# board.net
KiCad netlist of a schematic drawn in EAGLE
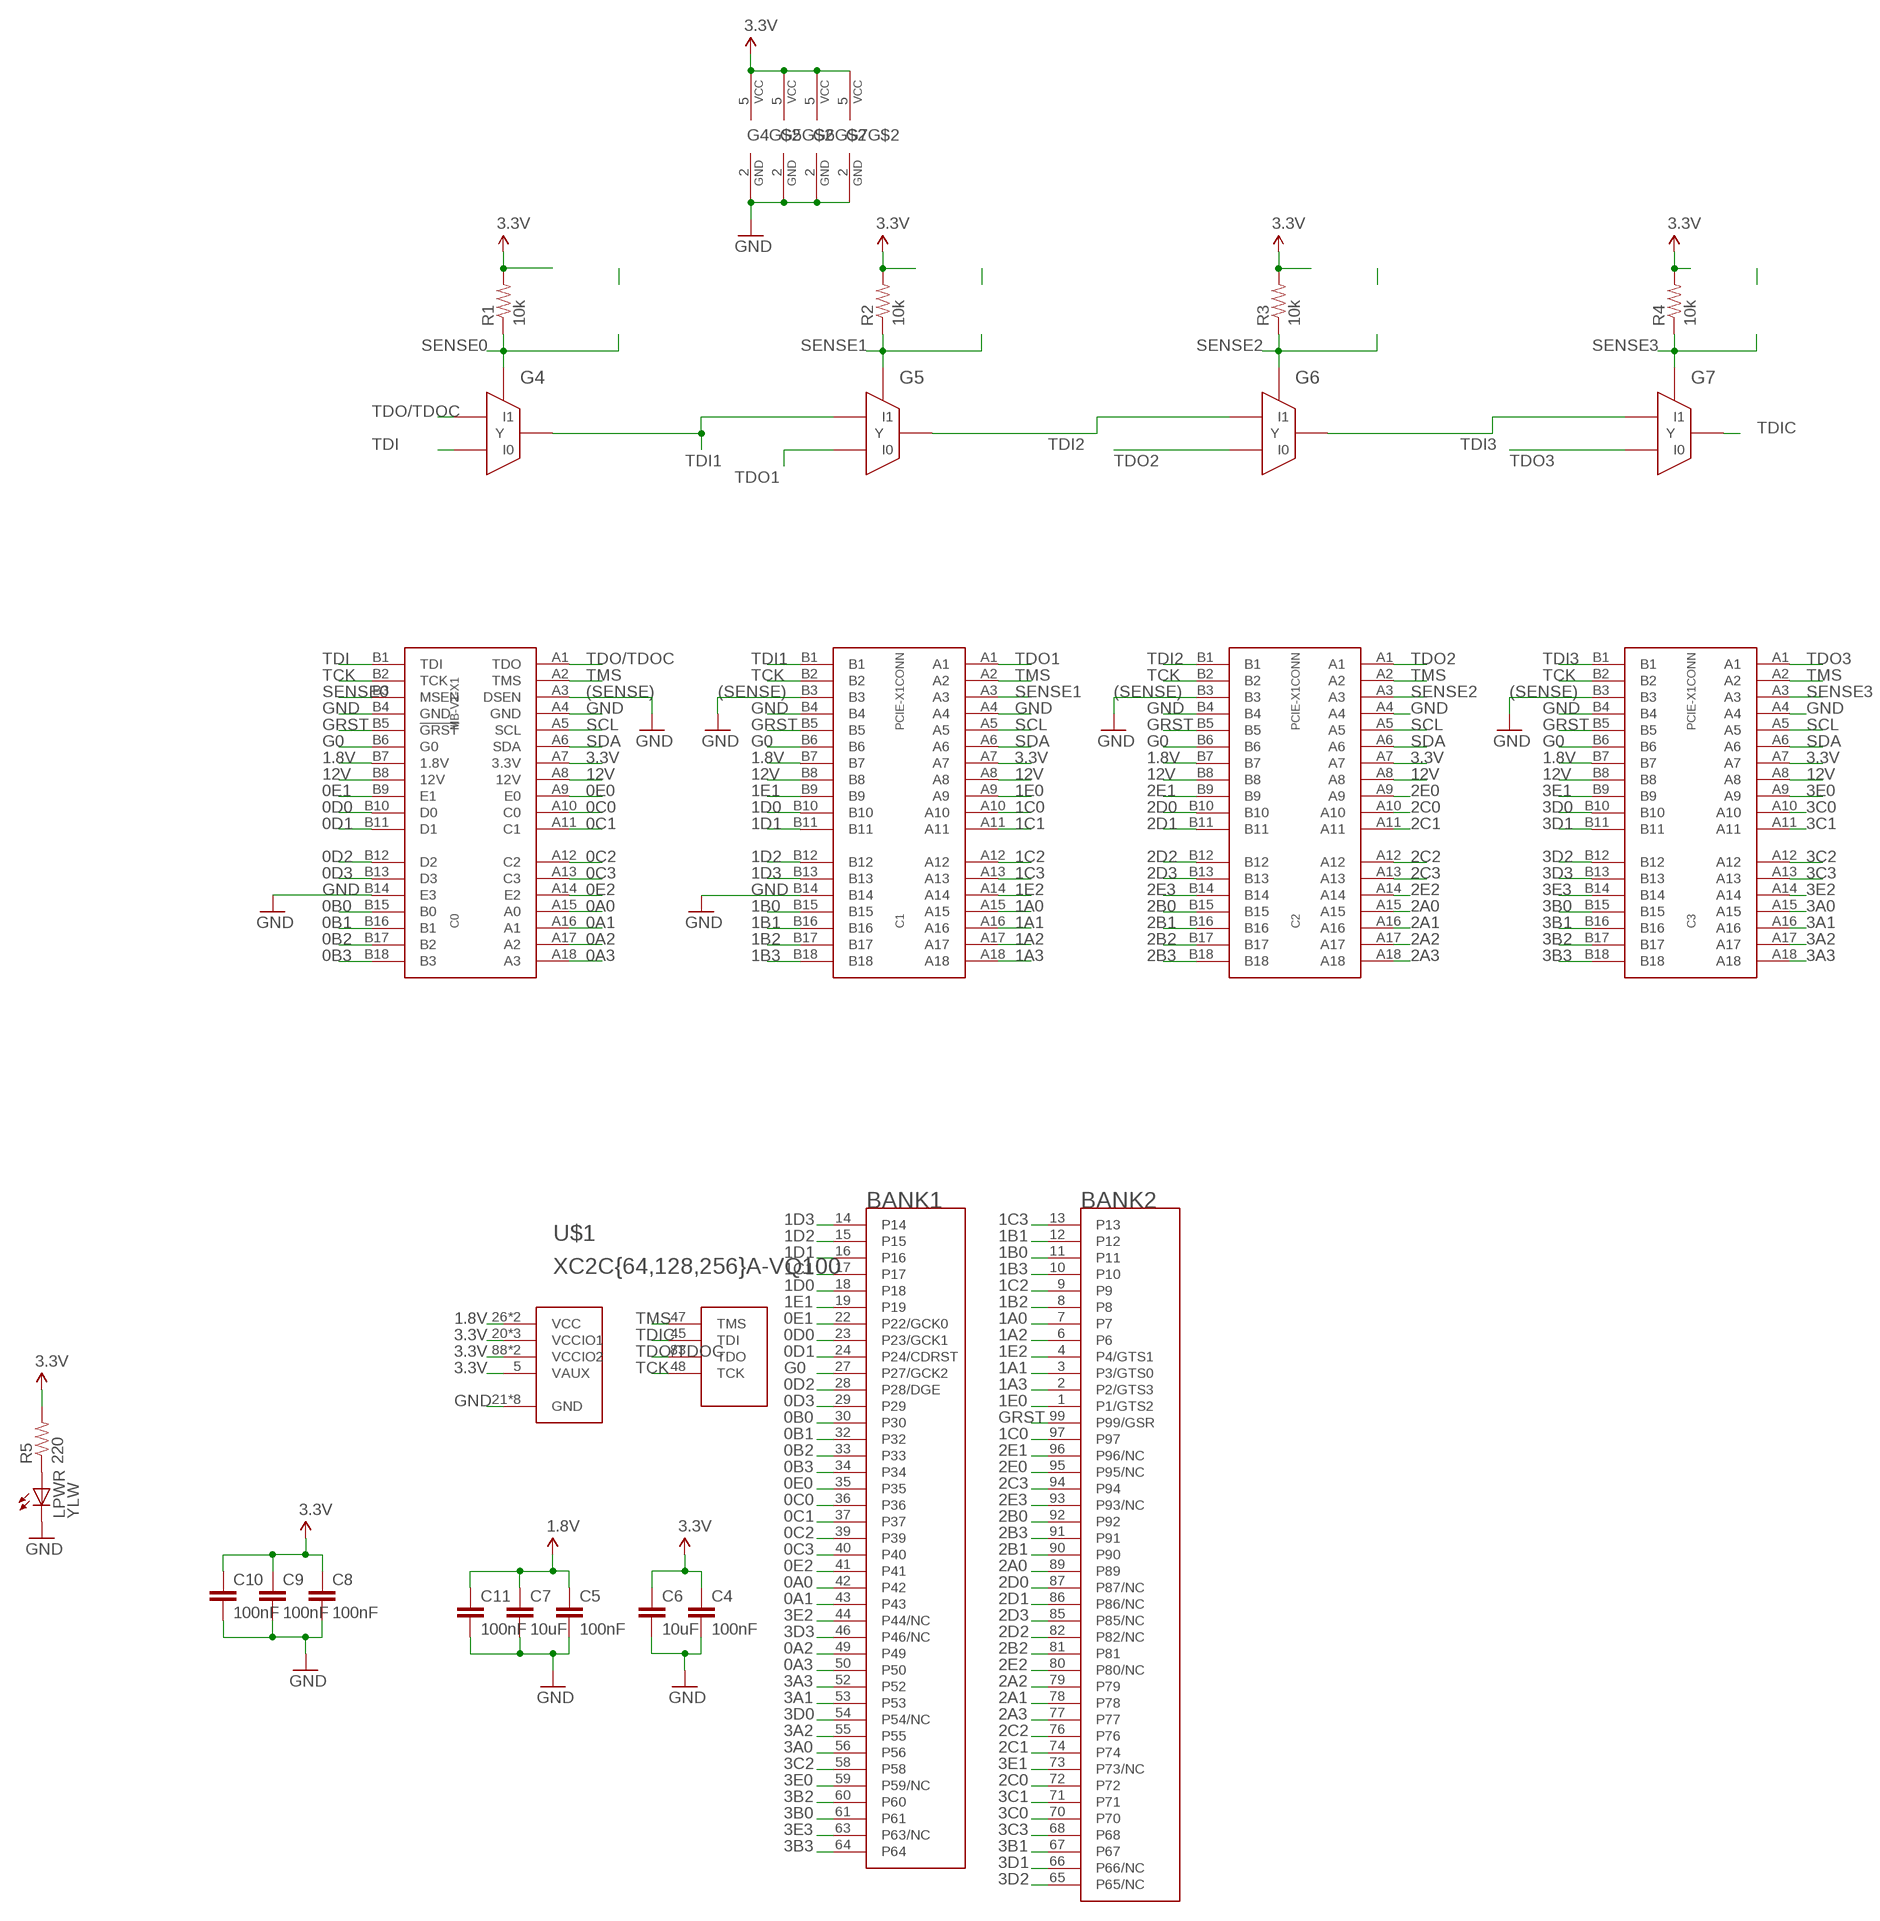
[diagram p0: schematic, sheet 1]

(export (version "E")
  (design (tool "Eeschema 10.0.6"))
  (components
    (comp (ref "C0")
      (value "MB-V1-X1")
      (footprint "eagle-import:PCIE-X1-EDGE")
      (libsource (lib "eagle-import") (part "MB-V1-X1"))
    )
    (comp (ref "C1")
      (value "PCIE-X1CONN")
      (footprint "eagle-import:PCIE-X1-CONN")
      (libsource (lib "eagle-import") (part "PCIE-X1CONN"))
    )
    (comp (ref "C2")
      (value "PCIE-X1CONN")
      (footprint "eagle-import:PCIE-X1-CONN")
      (libsource (lib "eagle-import") (part "PCIE-X1CONN"))
    )
    (comp (ref "C3")
      (value "PCIE-X1CONN")
      (footprint "eagle-import:PCIE-X1-CONN")
      (libsource (lib "eagle-import") (part "PCIE-X1CONN"))
    )
    (comp (ref "C4")
      (value "100nF")
      (footprint "eagle-import:0402-CAP")
      (libsource (lib "eagle-import") (part "CAP0402-CAP"))
    )
    (comp (ref "C5")
      (value "100nF")
      (footprint "eagle-import:0402-CAP")
      (libsource (lib "eagle-import") (part "CAP0402-CAP"))
    )
    (comp (ref "C6")
      (value "10uF")
      (footprint "eagle-import:0805")
      (libsource (lib "eagle-import") (part "CAP0805"))
    )
    (comp (ref "C7")
      (value "10uF")
      (footprint "eagle-import:0805")
      (libsource (lib "eagle-import") (part "CAP0805"))
    )
    (comp (ref "C8")
      (value "100nF")
      (footprint "eagle-import:0402-CAP")
      (libsource (lib "eagle-import") (part "CAP0402-CAP"))
    )
    (comp (ref "C9")
      (value "100nF")
      (footprint "eagle-import:0402-CAP")
      (libsource (lib "eagle-import") (part "CAP0402-CAP"))
    )
    (comp (ref "C10")
      (value "100nF")
      (footprint "eagle-import:0402-CAP")
      (libsource (lib "eagle-import") (part "CAP0402-CAP"))
    )
    (comp (ref "C11")
      (value "100nF")
      (footprint "eagle-import:0402-CAP")
      (libsource (lib "eagle-import") (part "CAP0402-CAP"))
    )
    (comp (ref "G4")
      (value "74G157")
      (footprint "eagle-import:SOT363")
      (libsource (lib "eagle-import") (part "74G157"))
    )
    (comp (ref "G5")
      (value "74G157")
      (footprint "eagle-import:SOT363")
      (libsource (lib "eagle-import") (part "74G157"))
    )
    (comp (ref "G6")
      (value "74G157")
      (footprint "eagle-import:SOT363")
      (libsource (lib "eagle-import") (part "74G157"))
    )
    (comp (ref "G7")
      (value "74G157")
      (footprint "eagle-import:SOT363")
      (libsource (lib "eagle-import") (part "74G157"))
    )
    (comp (ref "LPWR")
      (value "YLW")
      (footprint "eagle-import:LED-0603")
      (libsource (lib "eagle-import") (part "LED-RED0603"))
    )
    (comp (ref "R1")
      (value "10k")
      (footprint "eagle-import:0603-RES")
      (libsource (lib "eagle-import") (part "kmod-passives_RESISTOR0603"))
    )
    (comp (ref "R2")
      (value "10k")
      (footprint "eagle-import:0603-RES")
      (libsource (lib "eagle-import") (part "kmod-passives_RESISTOR0603"))
    )
    (comp (ref "R3")
      (value "10k")
      (footprint "eagle-import:0603-RES")
      (libsource (lib "eagle-import") (part "kmod-passives_RESISTOR0603"))
    )
    (comp (ref "R4")
      (value "10k")
      (footprint "eagle-import:0603-RES")
      (libsource (lib "eagle-import") (part "kmod-passives_RESISTOR0603"))
    )
    (comp (ref "R5")
      (value "220")
      (footprint "eagle-import:0603-RES")
      (libsource (lib "eagle-import") (part "RESISTOR0603"))
    )
    (comp (ref "U$1")
      (value "XC2C{64,128,256}A-VQ100")
      (footprint "eagle-import:XILINX_TQ100")
      (libsource (lib "eagle-import") (part "XC2C{64,128,256}A-VQ100"))
    )
  )
  (nets
    (net (code "1") (name "/0A0") (class "Default")
      (node (ref "C0") (pin "A15") (pinfunction "A0_A15") (pintype "bidirectional"))
      (node (ref "U$1") (pin "42") (pinfunction "P42_42") (pintype "bidirectional"))
    )
    (net (code "2") (name "/0A1") (class "Default")
      (node (ref "C0") (pin "A16") (pinfunction "A1_A16") (pintype "bidirectional"))
      (node (ref "U$1") (pin "43") (pinfunction "P43_43") (pintype "bidirectional"))
    )
    (net (code "3") (name "/0A2") (class "Default")
      (node (ref "C0") (pin "A17") (pinfunction "A2_A17") (pintype "bidirectional"))
      (node (ref "U$1") (pin "49") (pinfunction "P49_49") (pintype "bidirectional"))
    )
    (net (code "4") (name "/0A3") (class "Default")
      (node (ref "C0") (pin "A18") (pinfunction "A3_A18") (pintype "bidirectional"))
      (node (ref "U$1") (pin "50") (pinfunction "P50_50") (pintype "bidirectional"))
    )
    (net (code "5") (name "/0B0") (class "Default")
      (node (ref "C0") (pin "B15") (pinfunction "B0_B15") (pintype "bidirectional"))
      (node (ref "U$1") (pin "30") (pinfunction "P30_30") (pintype "bidirectional"))
    )
    (net (code "6") (name "/0B1") (class "Default")
      (node (ref "C0") (pin "B16") (pinfunction "B1_B16") (pintype "bidirectional"))
      (node (ref "U$1") (pin "32") (pinfunction "P32_32") (pintype "bidirectional"))
    )
    (net (code "7") (name "/0B2") (class "Default")
      (node (ref "C0") (pin "B17") (pinfunction "B2_B17") (pintype "bidirectional"))
      (node (ref "U$1") (pin "33") (pinfunction "P33_33") (pintype "bidirectional"))
    )
    (net (code "8") (name "/0B3") (class "Default")
      (node (ref "C0") (pin "B18") (pinfunction "B3_B18") (pintype "bidirectional"))
      (node (ref "U$1") (pin "34") (pinfunction "P34_34") (pintype "bidirectional"))
    )
    (net (code "9") (name "/0C0") (class "Default")
      (node (ref "C0") (pin "A10") (pinfunction "C0_A10") (pintype "bidirectional"))
      (node (ref "U$1") (pin "36") (pinfunction "P36_36") (pintype "bidirectional"))
    )
    (net (code "10") (name "/0C1") (class "Default")
      (node (ref "C0") (pin "A11") (pinfunction "C1_A11") (pintype "bidirectional"))
      (node (ref "U$1") (pin "37") (pinfunction "P37_37") (pintype "bidirectional"))
    )
    (net (code "11") (name "/0C2") (class "Default")
      (node (ref "C0") (pin "A12") (pinfunction "C2_A12") (pintype "bidirectional"))
      (node (ref "U$1") (pin "39") (pinfunction "P39_39") (pintype "bidirectional"))
    )
    (net (code "12") (name "/0C3") (class "Default")
      (node (ref "C0") (pin "A13") (pinfunction "C3_A13") (pintype "bidirectional"))
      (node (ref "U$1") (pin "40") (pinfunction "P40_40") (pintype "bidirectional"))
    )
    (net (code "13") (name "/0D0") (class "Default")
      (node (ref "C0") (pin "B10") (pinfunction "D0_B10") (pintype "bidirectional"))
      (node (ref "U$1") (pin "23") (pinfunction "P23/GCK1_23") (pintype "bidirectional"))
    )
    (net (code "14") (name "/0D1") (class "Default")
      (node (ref "C0") (pin "B11") (pinfunction "D1_B11") (pintype "bidirectional"))
      (node (ref "U$1") (pin "24") (pinfunction "P24/CDRST_24") (pintype "bidirectional"))
    )
    (net (code "15") (name "/0D2") (class "Default")
      (node (ref "C0") (pin "B12") (pinfunction "D2_B12") (pintype "bidirectional"))
      (node (ref "U$1") (pin "28") (pinfunction "P28/DGE_28") (pintype "bidirectional"))
    )
    (net (code "16") (name "/0D3") (class "Default")
      (node (ref "C0") (pin "B13") (pinfunction "D3_B13") (pintype "bidirectional"))
      (node (ref "U$1") (pin "29") (pinfunction "P29_29") (pintype "bidirectional"))
    )
    (net (code "17") (name "/0E0") (class "Default")
      (node (ref "C0") (pin "A9") (pinfunction "E0_A9") (pintype "bidirectional"))
      (node (ref "U$1") (pin "35") (pinfunction "P35_35") (pintype "bidirectional"))
    )
    (net (code "18") (name "/0E1") (class "Default")
      (node (ref "C0") (pin "B9") (pinfunction "E1_B9") (pintype "bidirectional"))
      (node (ref "U$1") (pin "22") (pinfunction "P22/GCK0_22") (pintype "bidirectional"))
    )
    (net (code "19") (name "/0E2") (class "Default")
      (node (ref "C0") (pin "A14") (pinfunction "E2_A14") (pintype "bidirectional"))
      (node (ref "U$1") (pin "41") (pinfunction "P41_41") (pintype "bidirectional"))
    )
    (net (code "20") (name "/1A0") (class "Default")
      (node (ref "C1") (pin "A15") (pinfunction "A15_A15") (pintype "bidirectional"))
      (node (ref "U$1") (pin "7") (pinfunction "P7_7") (pintype "bidirectional"))
    )
    (net (code "21") (name "/1A1") (class "Default")
      (node (ref "C1") (pin "A16") (pinfunction "A16_A16") (pintype "bidirectional"))
      (node (ref "U$1") (pin "3") (pinfunction "P3/GTS0_3") (pintype "bidirectional"))
    )
    (net (code "22") (name "/1A2") (class "Default")
      (node (ref "C1") (pin "A17") (pinfunction "A17_A17") (pintype "bidirectional"))
      (node (ref "U$1") (pin "6") (pinfunction "P6_6") (pintype "bidirectional"))
    )
    (net (code "23") (name "/1A3") (class "Default")
      (node (ref "C1") (pin "A18") (pinfunction "A18_A18") (pintype "bidirectional"))
      (node (ref "U$1") (pin "2") (pinfunction "P2/GTS3_2") (pintype "bidirectional"))
    )
    (net (code "24") (name "/1B0") (class "Default")
      (node (ref "C1") (pin "B15") (pinfunction "B15_B15") (pintype "bidirectional"))
      (node (ref "U$1") (pin "11") (pinfunction "P11_11") (pintype "bidirectional"))
    )
    (net (code "25") (name "/1B1") (class "Default")
      (node (ref "C1") (pin "B16") (pinfunction "B16_B16") (pintype "bidirectional"))
      (node (ref "U$1") (pin "12") (pinfunction "P12_12") (pintype "bidirectional"))
    )
    (net (code "26") (name "/1B2") (class "Default")
      (node (ref "C1") (pin "B17") (pinfunction "B17_B17") (pintype "bidirectional"))
      (node (ref "U$1") (pin "8") (pinfunction "P8_8") (pintype "bidirectional"))
    )
    (net (code "27") (name "/1B3") (class "Default")
      (node (ref "C1") (pin "B18") (pinfunction "B18_B18") (pintype "bidirectional"))
      (node (ref "U$1") (pin "10") (pinfunction "P10_10") (pintype "bidirectional"))
    )
    (net (code "28") (name "/1C0") (class "Default")
      (node (ref "C1") (pin "A10") (pinfunction "A10_A10") (pintype "bidirectional"))
      (node (ref "U$1") (pin "97") (pinfunction "P97_97") (pintype "bidirectional"))
    )
    (net (code "29") (name "/1C1") (class "Default")
      (node (ref "C1") (pin "A11") (pinfunction "A11_A11") (pintype "bidirectional"))
      (node (ref "U$1") (pin "17") (pinfunction "P17_17") (pintype "bidirectional"))
    )
    (net (code "30") (name "/1C2") (class "Default")
      (node (ref "C1") (pin "A12") (pinfunction "A12_A12") (pintype "bidirectional"))
      (node (ref "U$1") (pin "9") (pinfunction "P9_9") (pintype "bidirectional"))
    )
    (net (code "31") (name "/1C3") (class "Default")
      (node (ref "C1") (pin "A13") (pinfunction "A13_A13") (pintype "bidirectional"))
      (node (ref "U$1") (pin "13") (pinfunction "P13_13") (pintype "bidirectional"))
    )
    (net (code "32") (name "/1D0") (class "Default")
      (node (ref "C1") (pin "B10") (pinfunction "B10_B10") (pintype "bidirectional"))
      (node (ref "U$1") (pin "18") (pinfunction "P18_18") (pintype "bidirectional"))
    )
    (net (code "33") (name "/1D1") (class "Default")
      (node (ref "C1") (pin "B11") (pinfunction "B11_B11") (pintype "bidirectional"))
      (node (ref "U$1") (pin "16") (pinfunction "P16_16") (pintype "bidirectional"))
    )
    (net (code "34") (name "/1D2") (class "Default")
      (node (ref "C1") (pin "B12") (pinfunction "B12_B12") (pintype "bidirectional"))
      (node (ref "U$1") (pin "15") (pinfunction "P15_15") (pintype "bidirectional"))
    )
    (net (code "35") (name "/1D3") (class "Default")
      (node (ref "C1") (pin "B13") (pinfunction "B13_B13") (pintype "bidirectional"))
      (node (ref "U$1") (pin "14") (pinfunction "P14_14") (pintype "bidirectional"))
    )
    (net (code "36") (name "/1E0") (class "Default")
      (node (ref "C1") (pin "A9") (pinfunction "A9_A9") (pintype "bidirectional"))
      (node (ref "U$1") (pin "1") (pinfunction "P1/GTS2_1") (pintype "bidirectional"))
    )
    (net (code "37") (name "/1E1") (class "Default")
      (node (ref "C1") (pin "B9") (pinfunction "B9_B9") (pintype "bidirectional"))
      (node (ref "U$1") (pin "19") (pinfunction "P19_19") (pintype "bidirectional"))
    )
    (net (code "38") (name "/1E2") (class "Default")
      (node (ref "C1") (pin "A14") (pinfunction "A14_A14") (pintype "bidirectional"))
      (node (ref "U$1") (pin "4") (pinfunction "P4/GTS1_4") (pintype "bidirectional"))
    )
    (net (code "39") (name "/2A0") (class "Default")
      (node (ref "C2") (pin "A15") (pinfunction "A15_A15") (pintype "bidirectional"))
      (node (ref "U$1") (pin "89") (pinfunction "P89_89") (pintype "bidirectional"))
    )
    (net (code "40") (name "/2A1") (class "Default")
      (node (ref "C2") (pin "A16") (pinfunction "A16_A16") (pintype "bidirectional"))
      (node (ref "U$1") (pin "78") (pinfunction "P78_78") (pintype "bidirectional"))
    )
    (net (code "41") (name "/2A2") (class "Default")
      (node (ref "C2") (pin "A17") (pinfunction "A17_A17") (pintype "bidirectional"))
      (node (ref "U$1") (pin "79") (pinfunction "P79_79") (pintype "bidirectional"))
    )
    (net (code "42") (name "/2A3") (class "Default")
      (node (ref "C2") (pin "A18") (pinfunction "A18_A18") (pintype "bidirectional"))
      (node (ref "U$1") (pin "77") (pinfunction "P77_77") (pintype "bidirectional"))
    )
    (net (code "43") (name "/2B0") (class "Default")
      (node (ref "C2") (pin "B15") (pinfunction "B15_B15") (pintype "bidirectional"))
      (node (ref "U$1") (pin "92") (pinfunction "P92_92") (pintype "bidirectional"))
    )
    (net (code "44") (name "/2B1") (class "Default")
      (node (ref "C2") (pin "B16") (pinfunction "B16_B16") (pintype "bidirectional"))
      (node (ref "U$1") (pin "90") (pinfunction "P90_90") (pintype "bidirectional"))
    )
    (net (code "45") (name "/2B2") (class "Default")
      (node (ref "C2") (pin "B17") (pinfunction "B17_B17") (pintype "bidirectional"))
      (node (ref "U$1") (pin "81") (pinfunction "P81_81") (pintype "bidirectional"))
    )
    (net (code "46") (name "/2B3") (class "Default")
      (node (ref "C2") (pin "B18") (pinfunction "B18_B18") (pintype "bidirectional"))
      (node (ref "U$1") (pin "91") (pinfunction "P91_91") (pintype "bidirectional"))
    )
    (net (code "47") (name "/2C0") (class "Default")
      (node (ref "C2") (pin "A10") (pinfunction "A10_A10") (pintype "bidirectional"))
      (node (ref "U$1") (pin "72") (pinfunction "P72_72") (pintype "bidirectional"))
    )
    (net (code "48") (name "/2C1") (class "Default")
      (node (ref "C2") (pin "A11") (pinfunction "A11_A11") (pintype "bidirectional"))
      (node (ref "U$1") (pin "74") (pinfunction "P74_74") (pintype "bidirectional"))
    )
    (net (code "49") (name "/2C2") (class "Default")
      (node (ref "C2") (pin "A12") (pinfunction "A12_A12") (pintype "bidirectional"))
      (node (ref "U$1") (pin "76") (pinfunction "P76_76") (pintype "bidirectional"))
    )
    (net (code "50") (name "/2C3") (class "Default")
      (node (ref "C2") (pin "A13") (pinfunction "A13_A13") (pintype "bidirectional"))
      (node (ref "U$1") (pin "94") (pinfunction "P94_94") (pintype "bidirectional"))
    )
    (net (code "51") (name "/2D0") (class "Default")
      (node (ref "C2") (pin "B10") (pinfunction "B10_B10") (pintype "bidirectional"))
      (node (ref "U$1") (pin "87") (pinfunction "P87/NC_87") (pintype "bidirectional"))
    )
    (net (code "52") (name "/2D1") (class "Default")
      (node (ref "C2") (pin "B11") (pinfunction "B11_B11") (pintype "bidirectional"))
      (node (ref "U$1") (pin "86") (pinfunction "P86/NC_86") (pintype "bidirectional"))
    )
    (net (code "53") (name "/2D2") (class "Default")
      (node (ref "C2") (pin "B12") (pinfunction "B12_B12") (pintype "bidirectional"))
      (node (ref "U$1") (pin "82") (pinfunction "P82/NC_82") (pintype "bidirectional"))
    )
    (net (code "54") (name "/2D3") (class "Default")
      (node (ref "C2") (pin "B13") (pinfunction "B13_B13") (pintype "bidirectional"))
      (node (ref "U$1") (pin "85") (pinfunction "P85/NC_85") (pintype "bidirectional"))
    )
    (net (code "55") (name "/2E0") (class "Default")
      (node (ref "C2") (pin "A9") (pinfunction "A9_A9") (pintype "bidirectional"))
      (node (ref "U$1") (pin "95") (pinfunction "P95/NC_95") (pintype "bidirectional"))
    )
    (net (code "56") (name "/2E1") (class "Default")
      (node (ref "C2") (pin "B9") (pinfunction "B9_B9") (pintype "bidirectional"))
      (node (ref "U$1") (pin "96") (pinfunction "P96/NC_96") (pintype "bidirectional"))
    )
    (net (code "57") (name "/2E2") (class "Default")
      (node (ref "C2") (pin "A14") (pinfunction "A14_A14") (pintype "bidirectional"))
      (node (ref "U$1") (pin "80") (pinfunction "P80/NC_80") (pintype "bidirectional"))
    )
    (net (code "58") (name "/2E3") (class "Default")
      (node (ref "C2") (pin "B14") (pinfunction "B14_B14") (pintype "bidirectional"))
      (node (ref "U$1") (pin "93") (pinfunction "P93/NC_93") (pintype "bidirectional"))
    )
    (net (code "59") (name "/3A0") (class "Default")
      (node (ref "C3") (pin "A15") (pinfunction "A15_A15") (pintype "bidirectional"))
      (node (ref "U$1") (pin "56") (pinfunction "P56_56") (pintype "bidirectional"))
    )
    (net (code "60") (name "/3A1") (class "Default")
      (node (ref "C3") (pin "A16") (pinfunction "A16_A16") (pintype "bidirectional"))
      (node (ref "U$1") (pin "53") (pinfunction "P53_53") (pintype "bidirectional"))
    )
    (net (code "61") (name "/3A2") (class "Default")
      (node (ref "C3") (pin "A17") (pinfunction "A17_A17") (pintype "bidirectional"))
      (node (ref "U$1") (pin "55") (pinfunction "P55_55") (pintype "bidirectional"))
    )
    (net (code "62") (name "/3A3") (class "Default")
      (node (ref "C3") (pin "A18") (pinfunction "A18_A18") (pintype "bidirectional"))
      (node (ref "U$1") (pin "52") (pinfunction "P52_52") (pintype "bidirectional"))
    )
    (net (code "63") (name "/3B0") (class "Default")
      (node (ref "C3") (pin "B15") (pinfunction "B15_B15") (pintype "bidirectional"))
      (node (ref "U$1") (pin "61") (pinfunction "P61_61") (pintype "bidirectional"))
    )
    (net (code "64") (name "/3B1") (class "Default")
      (node (ref "C3") (pin "B16") (pinfunction "B16_B16") (pintype "bidirectional"))
      (node (ref "U$1") (pin "67") (pinfunction "P67_67") (pintype "bidirectional"))
    )
    (net (code "65") (name "/3B2") (class "Default")
      (node (ref "C3") (pin "B17") (pinfunction "B17_B17") (pintype "bidirectional"))
      (node (ref "U$1") (pin "60") (pinfunction "P60_60") (pintype "bidirectional"))
    )
    (net (code "66") (name "/3B3") (class "Default")
      (node (ref "C3") (pin "B18") (pinfunction "B18_B18") (pintype "bidirectional"))
      (node (ref "U$1") (pin "64") (pinfunction "P64_64") (pintype "bidirectional"))
    )
    (net (code "67") (name "/3C0") (class "Default")
      (node (ref "C3") (pin "A10") (pinfunction "A10_A10") (pintype "bidirectional"))
      (node (ref "U$1") (pin "70") (pinfunction "P70_70") (pintype "bidirectional"))
    )
    (net (code "68") (name "/3C1") (class "Default")
      (node (ref "C3") (pin "A11") (pinfunction "A11_A11") (pintype "bidirectional"))
      (node (ref "U$1") (pin "71") (pinfunction "P71_71") (pintype "bidirectional"))
    )
    (net (code "69") (name "/3C2") (class "Default")
      (node (ref "C3") (pin "A12") (pinfunction "A12_A12") (pintype "bidirectional"))
      (node (ref "U$1") (pin "58") (pinfunction "P58_58") (pintype "bidirectional"))
    )
    (net (code "70") (name "/3C3") (class "Default")
      (node (ref "C3") (pin "A13") (pinfunction "A13_A13") (pintype "bidirectional"))
      (node (ref "U$1") (pin "68") (pinfunction "P68_68") (pintype "bidirectional"))
    )
    (net (code "71") (name "/3D0") (class "Default")
      (node (ref "C3") (pin "B10") (pinfunction "B10_B10") (pintype "bidirectional"))
      (node (ref "U$1") (pin "54") (pinfunction "P54/NC_54") (pintype "bidirectional"))
    )
    (net (code "72") (name "/3D1") (class "Default")
      (node (ref "C3") (pin "B11") (pinfunction "B11_B11") (pintype "bidirectional"))
      (node (ref "U$1") (pin "66") (pinfunction "P66/NC_66") (pintype "bidirectional"))
    )
    (net (code "73") (name "/3D2") (class "Default")
      (node (ref "C3") (pin "B12") (pinfunction "B12_B12") (pintype "bidirectional"))
      (node (ref "U$1") (pin "65") (pinfunction "P65/NC_65") (pintype "bidirectional"))
    )
    (net (code "74") (name "/3D3") (class "Default")
      (node (ref "C3") (pin "B13") (pinfunction "B13_B13") (pintype "bidirectional"))
      (node (ref "U$1") (pin "46") (pinfunction "P46/NC_46") (pintype "bidirectional"))
    )
    (net (code "75") (name "/3E0") (class "Default")
      (node (ref "C3") (pin "A9") (pinfunction "A9_A9") (pintype "bidirectional"))
      (node (ref "U$1") (pin "59") (pinfunction "P59/NC_59") (pintype "bidirectional"))
    )
    (net (code "76") (name "/3E1") (class "Default")
      (node (ref "C3") (pin "B9") (pinfunction "B9_B9") (pintype "bidirectional"))
      (node (ref "U$1") (pin "73") (pinfunction "P73/NC_73") (pintype "bidirectional"))
    )
    (net (code "77") (name "/3E2") (class "Default")
      (node (ref "C3") (pin "A14") (pinfunction "A14_A14") (pintype "bidirectional"))
      (node (ref "U$1") (pin "44") (pinfunction "P44/NC_44") (pintype "bidirectional"))
    )
    (net (code "78") (name "/3E3") (class "Default")
      (node (ref "C3") (pin "B14") (pinfunction "B14_B14") (pintype "bidirectional"))
      (node (ref "U$1") (pin "63") (pinfunction "P63/NC_63") (pintype "bidirectional"))
    )
    (net (code "79") (name "/12V") (class "Default")
      (node (ref "C0") (pin "A8") (pinfunction "12V_A8") (pintype "bidirectional"))
      (node (ref "C0") (pin "B8") (pinfunction "12V_B8") (pintype "bidirectional"))
      (node (ref "C1") (pin "A8") (pinfunction "A8_A8") (pintype "bidirectional"))
      (node (ref "C1") (pin "B8") (pinfunction "B8_B8") (pintype "bidirectional"))
      (node (ref "C2") (pin "A8") (pinfunction "A8_A8") (pintype "bidirectional"))
      (node (ref "C2") (pin "B8") (pinfunction "B8_B8") (pintype "bidirectional"))
      (node (ref "C3") (pin "A8") (pinfunction "A8_A8") (pintype "bidirectional"))
      (node (ref "C3") (pin "B8") (pinfunction "B8_B8") (pintype "bidirectional"))
    )
    (net (code "80") (name "/G0") (class "Default")
      (node (ref "C0") (pin "B6") (pinfunction "G0_B6") (pintype "bidirectional"))
      (node (ref "C1") (pin "B6") (pinfunction "B6_B6") (pintype "bidirectional"))
      (node (ref "C2") (pin "B6") (pinfunction "B6_B6") (pintype "bidirectional"))
      (node (ref "C3") (pin "B6") (pinfunction "B6_B6") (pintype "bidirectional"))
      (node (ref "U$1") (pin "27") (pinfunction "P27/GCK2_27") (pintype "bidirectional"))
    )
    (net (code "81") (name "/GRST") (class "Default")
      (node (ref "C0") (pin "B5") (pinfunction "~{GRST}_B5") (pintype "bidirectional"))
      (node (ref "C1") (pin "B5") (pinfunction "B5_B5") (pintype "bidirectional"))
      (node (ref "C2") (pin "B5") (pinfunction "B5_B5") (pintype "bidirectional"))
      (node (ref "C3") (pin "B5") (pinfunction "B5_B5") (pintype "bidirectional"))
      (node (ref "U$1") (pin "99") (pinfunction "P99/GSR_99") (pintype "bidirectional"))
    )
    (net (code "82") (name "/SCL") (class "Default")
      (node (ref "C0") (pin "A5") (pinfunction "SCL_A5") (pintype "bidirectional"))
      (node (ref "C1") (pin "A5") (pinfunction "A5_A5") (pintype "bidirectional"))
      (node (ref "C2") (pin "A5") (pinfunction "A5_A5") (pintype "bidirectional"))
      (node (ref "C3") (pin "A5") (pinfunction "A5_A5") (pintype "bidirectional"))
    )
    (net (code "83") (name "/SDA") (class "Default")
      (node (ref "C0") (pin "A6") (pinfunction "SDA_A6") (pintype "bidirectional"))
      (node (ref "C1") (pin "A6") (pinfunction "A6_A6") (pintype "bidirectional"))
      (node (ref "C2") (pin "A6") (pinfunction "A6_A6") (pintype "bidirectional"))
      (node (ref "C3") (pin "A6") (pinfunction "A6_A6") (pintype "bidirectional"))
    )
    (net (code "84") (name "/SENSE0") (class "Default")
      (node (ref "C0") (pin "B3") (pinfunction "MSEN_B3") (pintype "bidirectional"))
      (node (ref "G4") (pin "6") (pinfunction "S_6") (pintype "input"))
      (node (ref "R1") (pin "1") (pinfunction "1_1") (pintype "passive"))
    )
    (net (code "85") (name "/SENSE1") (class "Default")
      (node (ref "C1") (pin "A3") (pinfunction "A3_A3") (pintype "bidirectional"))
      (node (ref "G5") (pin "6") (pinfunction "S_6") (pintype "input"))
      (node (ref "R2") (pin "1") (pinfunction "1_1") (pintype "passive"))
    )
    (net (code "86") (name "/SENSE2") (class "Default")
      (node (ref "C2") (pin "A3") (pinfunction "A3_A3") (pintype "bidirectional"))
      (node (ref "G6") (pin "6") (pinfunction "S_6") (pintype "input"))
      (node (ref "R3") (pin "1") (pinfunction "1_1") (pintype "passive"))
    )
    (net (code "87") (name "/SENSE3") (class "Default")
      (node (ref "C3") (pin "A3") (pinfunction "A3_A3") (pintype "bidirectional"))
      (node (ref "G7") (pin "6") (pinfunction "S_6") (pintype "input"))
      (node (ref "R4") (pin "1") (pinfunction "1_1") (pintype "passive"))
    )
    (net (code "88") (name "/TCK") (class "Default")
      (node (ref "C0") (pin "B2") (pinfunction "TCK_B2") (pintype "bidirectional"))
      (node (ref "C1") (pin "B2") (pinfunction "B2_B2") (pintype "bidirectional"))
      (node (ref "C2") (pin "B2") (pinfunction "B2_B2") (pintype "bidirectional"))
      (node (ref "C3") (pin "B2") (pinfunction "B2_B2") (pintype "bidirectional"))
      (node (ref "U$1") (pin "48") (pinfunction "TCK_48") (pintype "bidirectional"))
    )
    (net (code "89") (name "/TDI") (class "Default")
      (node (ref "C0") (pin "B1") (pinfunction "TDI_B1") (pintype "bidirectional"))
      (node (ref "G4") (pin "3") (pinfunction "I0_3") (pintype "input"))
    )
    (net (code "90") (name "/TDI1") (class "Default")
      (node (ref "C1") (pin "B1") (pinfunction "B1_B1") (pintype "bidirectional"))
      (node (ref "G4") (pin "4") (pinfunction "Y_4") (pintype "output"))
      (node (ref "G5") (pin "1") (pinfunction "I1_1") (pintype "input"))
    )
    (net (code "91") (name "/TDI2") (class "Default")
      (node (ref "C2") (pin "B1") (pinfunction "B1_B1") (pintype "bidirectional"))
      (node (ref "G5") (pin "4") (pinfunction "Y_4") (pintype "output"))
      (node (ref "G6") (pin "1") (pinfunction "I1_1") (pintype "input"))
    )
    (net (code "92") (name "/TDI3") (class "Default")
      (node (ref "C3") (pin "B1") (pinfunction "B1_B1") (pintype "bidirectional"))
      (node (ref "G6") (pin "4") (pinfunction "Y_4") (pintype "output"))
      (node (ref "G7") (pin "1") (pinfunction "I1_1") (pintype "input"))
    )
    (net (code "93") (name "/TDIC") (class "Default")
      (node (ref "G7") (pin "4") (pinfunction "Y_4") (pintype "output"))
      (node (ref "U$1") (pin "45") (pinfunction "TDI_45") (pintype "bidirectional"))
    )
    (net (code "94") (name "/TDO1") (class "Default")
      (node (ref "C1") (pin "A1") (pinfunction "A1_A1") (pintype "bidirectional"))
      (node (ref "G5") (pin "3") (pinfunction "I0_3") (pintype "input"))
    )
    (net (code "95") (name "/TDO2") (class "Default")
      (node (ref "C2") (pin "A1") (pinfunction "A1_A1") (pintype "bidirectional"))
      (node (ref "G6") (pin "3") (pinfunction "I0_3") (pintype "input"))
    )
    (net (code "96") (name "/TDO3") (class "Default")
      (node (ref "C3") (pin "A1") (pinfunction "A1_A1") (pintype "bidirectional"))
      (node (ref "G7") (pin "3") (pinfunction "I0_3") (pintype "input"))
    )
    (net (code "97") (name "/TDO{slash}TDOC") (class "Default")
      (node (ref "C0") (pin "A1") (pinfunction "TDO_A1") (pintype "bidirectional"))
      (node (ref "G4") (pin "1") (pinfunction "I1_1") (pintype "input"))
      (node (ref "U$1") (pin "83") (pinfunction "TDO_83") (pintype "bidirectional"))
    )
    (net (code "98") (name "/TMS") (class "Default")
      (node (ref "C0") (pin "A2") (pinfunction "TMS_A2") (pintype "bidirectional"))
      (node (ref "C1") (pin "A2") (pinfunction "A2_A2") (pintype "bidirectional"))
      (node (ref "C2") (pin "A2") (pinfunction "A2_A2") (pintype "bidirectional"))
      (node (ref "C3") (pin "A2") (pinfunction "A2_A2") (pintype "bidirectional"))
      (node (ref "U$1") (pin "47") (pinfunction "TMS_47") (pintype "bidirectional"))
    )
    (net (code "99") (name "1.8V") (class "Default")
      (node (ref "C0") (pin "B7") (pinfunction "1.8V_B7") (pintype "bidirectional"))
      (node (ref "C1") (pin "B7") (pinfunction "B7_B7") (pintype "bidirectional"))
      (node (ref "C11") (pin "1") (pinfunction "1_1") (pintype "passive"))
      (node (ref "C2") (pin "B7") (pinfunction "B7_B7") (pintype "bidirectional"))
      (node (ref "C3") (pin "B7") (pinfunction "B7_B7") (pintype "bidirectional"))
      (node (ref "C5") (pin "1") (pinfunction "1_1") (pintype "passive"))
      (node (ref "C7") (pin "1") (pinfunction "1_1") (pintype "passive"))
      (node (ref "U$1") (pin "26") (pinfunction "VCC_26") (pintype "bidirectional"))
      (node (ref "U$1") (pin "57") (pinfunction "VCC_57") (pintype "bidirectional"))
    )
    (net (code "100") (name "3.3V") (class "Default")
      (node (ref "C0") (pin "A7") (pinfunction "3.3V_A7") (pintype "bidirectional"))
      (node (ref "C1") (pin "A7") (pinfunction "A7_A7") (pintype "bidirectional"))
      (node (ref "C10") (pin "1") (pinfunction "1_1") (pintype "passive"))
      (node (ref "C2") (pin "A7") (pinfunction "A7_A7") (pintype "bidirectional"))
      (node (ref "C3") (pin "A7") (pinfunction "A7_A7") (pintype "bidirectional"))
      (node (ref "C4") (pin "1") (pinfunction "1_1") (pintype "passive"))
      (node (ref "C6") (pin "1") (pinfunction "1_1") (pintype "passive"))
      (node (ref "C8") (pin "1") (pinfunction "1_1") (pintype "passive"))
      (node (ref "C9") (pin "1") (pinfunction "1_1") (pintype "passive"))
      (node (ref "G4") (pin "5") (pinfunction "VCC_5") (pintype "power_in"))
      (node (ref "G5") (pin "5") (pinfunction "VCC_5") (pintype "power_in"))
      (node (ref "G6") (pin "5") (pinfunction "VCC_5") (pintype "power_in"))
      (node (ref "G7") (pin "5") (pinfunction "VCC_5") (pintype "power_in"))
      (node (ref "R1") (pin "2") (pinfunction "2_2") (pintype "passive"))
      (node (ref "R2") (pin "2") (pinfunction "2_2") (pintype "passive"))
      (node (ref "R3") (pin "2") (pinfunction "2_2") (pintype "passive"))
      (node (ref "R4") (pin "2") (pinfunction "2_2") (pintype "passive"))
      (node (ref "R5") (pin "2") (pinfunction "2_2") (pintype "passive"))
      (node (ref "U$1") (pin "20") (pinfunction "VCCIO1_20") (pintype "bidirectional"))
      (node (ref "U$1") (pin "38") (pinfunction "VCCIO1_38") (pintype "bidirectional"))
      (node (ref "U$1") (pin "5") (pinfunction "VAUX_5") (pintype "bidirectional"))
      (node (ref "U$1") (pin "51") (pinfunction "VCCIO1_51") (pintype "bidirectional"))
      (node (ref "U$1") (pin "88") (pinfunction "VCCIO2_88") (pintype "bidirectional"))
      (node (ref "U$1") (pin "98") (pinfunction "VCCIO2_98") (pintype "bidirectional"))
    )
    (net (code "101") (name "GND") (class "Default")
      (node (ref "C0") (pin "A3") (pinfunction "DSEN_A3") (pintype "bidirectional"))
      (node (ref "C0") (pin "A4") (pinfunction "GND_A4") (pintype "bidirectional"))
      (node (ref "C0") (pin "B14") (pinfunction "E3_B14") (pintype "bidirectional"))
      (node (ref "C0") (pin "B4") (pinfunction "GND_B4") (pintype "bidirectional"))
      (node (ref "C1") (pin "A4") (pinfunction "A4_A4") (pintype "bidirectional"))
      (node (ref "C1") (pin "B14") (pinfunction "B14_B14") (pintype "bidirectional"))
      (node (ref "C1") (pin "B3") (pinfunction "B3_B3") (pintype "bidirectional"))
      (node (ref "C1") (pin "B4") (pinfunction "B4_B4") (pintype "bidirectional"))
      (node (ref "C10") (pin "2") (pinfunction "2_2") (pintype "passive"))
      (node (ref "C11") (pin "2") (pinfunction "2_2") (pintype "passive"))
      (node (ref "C2") (pin "A4") (pinfunction "A4_A4") (pintype "bidirectional"))
      (node (ref "C2") (pin "B3") (pinfunction "B3_B3") (pintype "bidirectional"))
      (node (ref "C2") (pin "B4") (pinfunction "B4_B4") (pintype "bidirectional"))
      (node (ref "C3") (pin "A4") (pinfunction "A4_A4") (pintype "bidirectional"))
      (node (ref "C3") (pin "B3") (pinfunction "B3_B3") (pintype "bidirectional"))
      (node (ref "C3") (pin "B4") (pinfunction "B4_B4") (pintype "bidirectional"))
      (node (ref "C4") (pin "2") (pinfunction "2_2") (pintype "passive"))
      (node (ref "C5") (pin "2") (pinfunction "2_2") (pintype "passive"))
      (node (ref "C6") (pin "2") (pinfunction "2_2") (pintype "passive"))
      (node (ref "C7") (pin "2") (pinfunction "2_2") (pintype "passive"))
      (node (ref "C8") (pin "2") (pinfunction "2_2") (pintype "passive"))
      (node (ref "C9") (pin "2") (pinfunction "2_2") (pintype "passive"))
      (node (ref "G4") (pin "2") (pinfunction "GND_2") (pintype "power_in"))
      (node (ref "G5") (pin "2") (pinfunction "GND_2") (pintype "power_in"))
      (node (ref "G6") (pin "2") (pinfunction "GND_2") (pintype "power_in"))
      (node (ref "G7") (pin "2") (pinfunction "GND_2") (pintype "power_in"))
      (node (ref "LPWR") (pin "C") (pinfunction "C_C") (pintype "passive"))
      (node (ref "U$1") (pin "100") (pinfunction "GND_100") (pintype "bidirectional"))
      (node (ref "U$1") (pin "21") (pinfunction "GND_21") (pintype "bidirectional"))
      (node (ref "U$1") (pin "25") (pinfunction "GND_25") (pintype "bidirectional"))
      (node (ref "U$1") (pin "31") (pinfunction "GND_31") (pintype "bidirectional"))
      (node (ref "U$1") (pin "62") (pinfunction "GND_62") (pintype "bidirectional"))
      (node (ref "U$1") (pin "69") (pinfunction "GND_69") (pintype "bidirectional"))
      (node (ref "U$1") (pin "75") (pinfunction "GND_75") (pintype "bidirectional"))
      (node (ref "U$1") (pin "84") (pinfunction "GND_84") (pintype "bidirectional"))
    )
    (net (code "102") (name "Net-(LPWR-PadA)") (class "Default")
      (node (ref "LPWR") (pin "A") (pinfunction "A_A") (pintype "passive"))
      (node (ref "R5") (pin "1") (pinfunction "1_1") (pintype "passive"))
    )
  )
)
